# Sheet1.net
KiCad netlist of a schematic drawn in Altium Designer
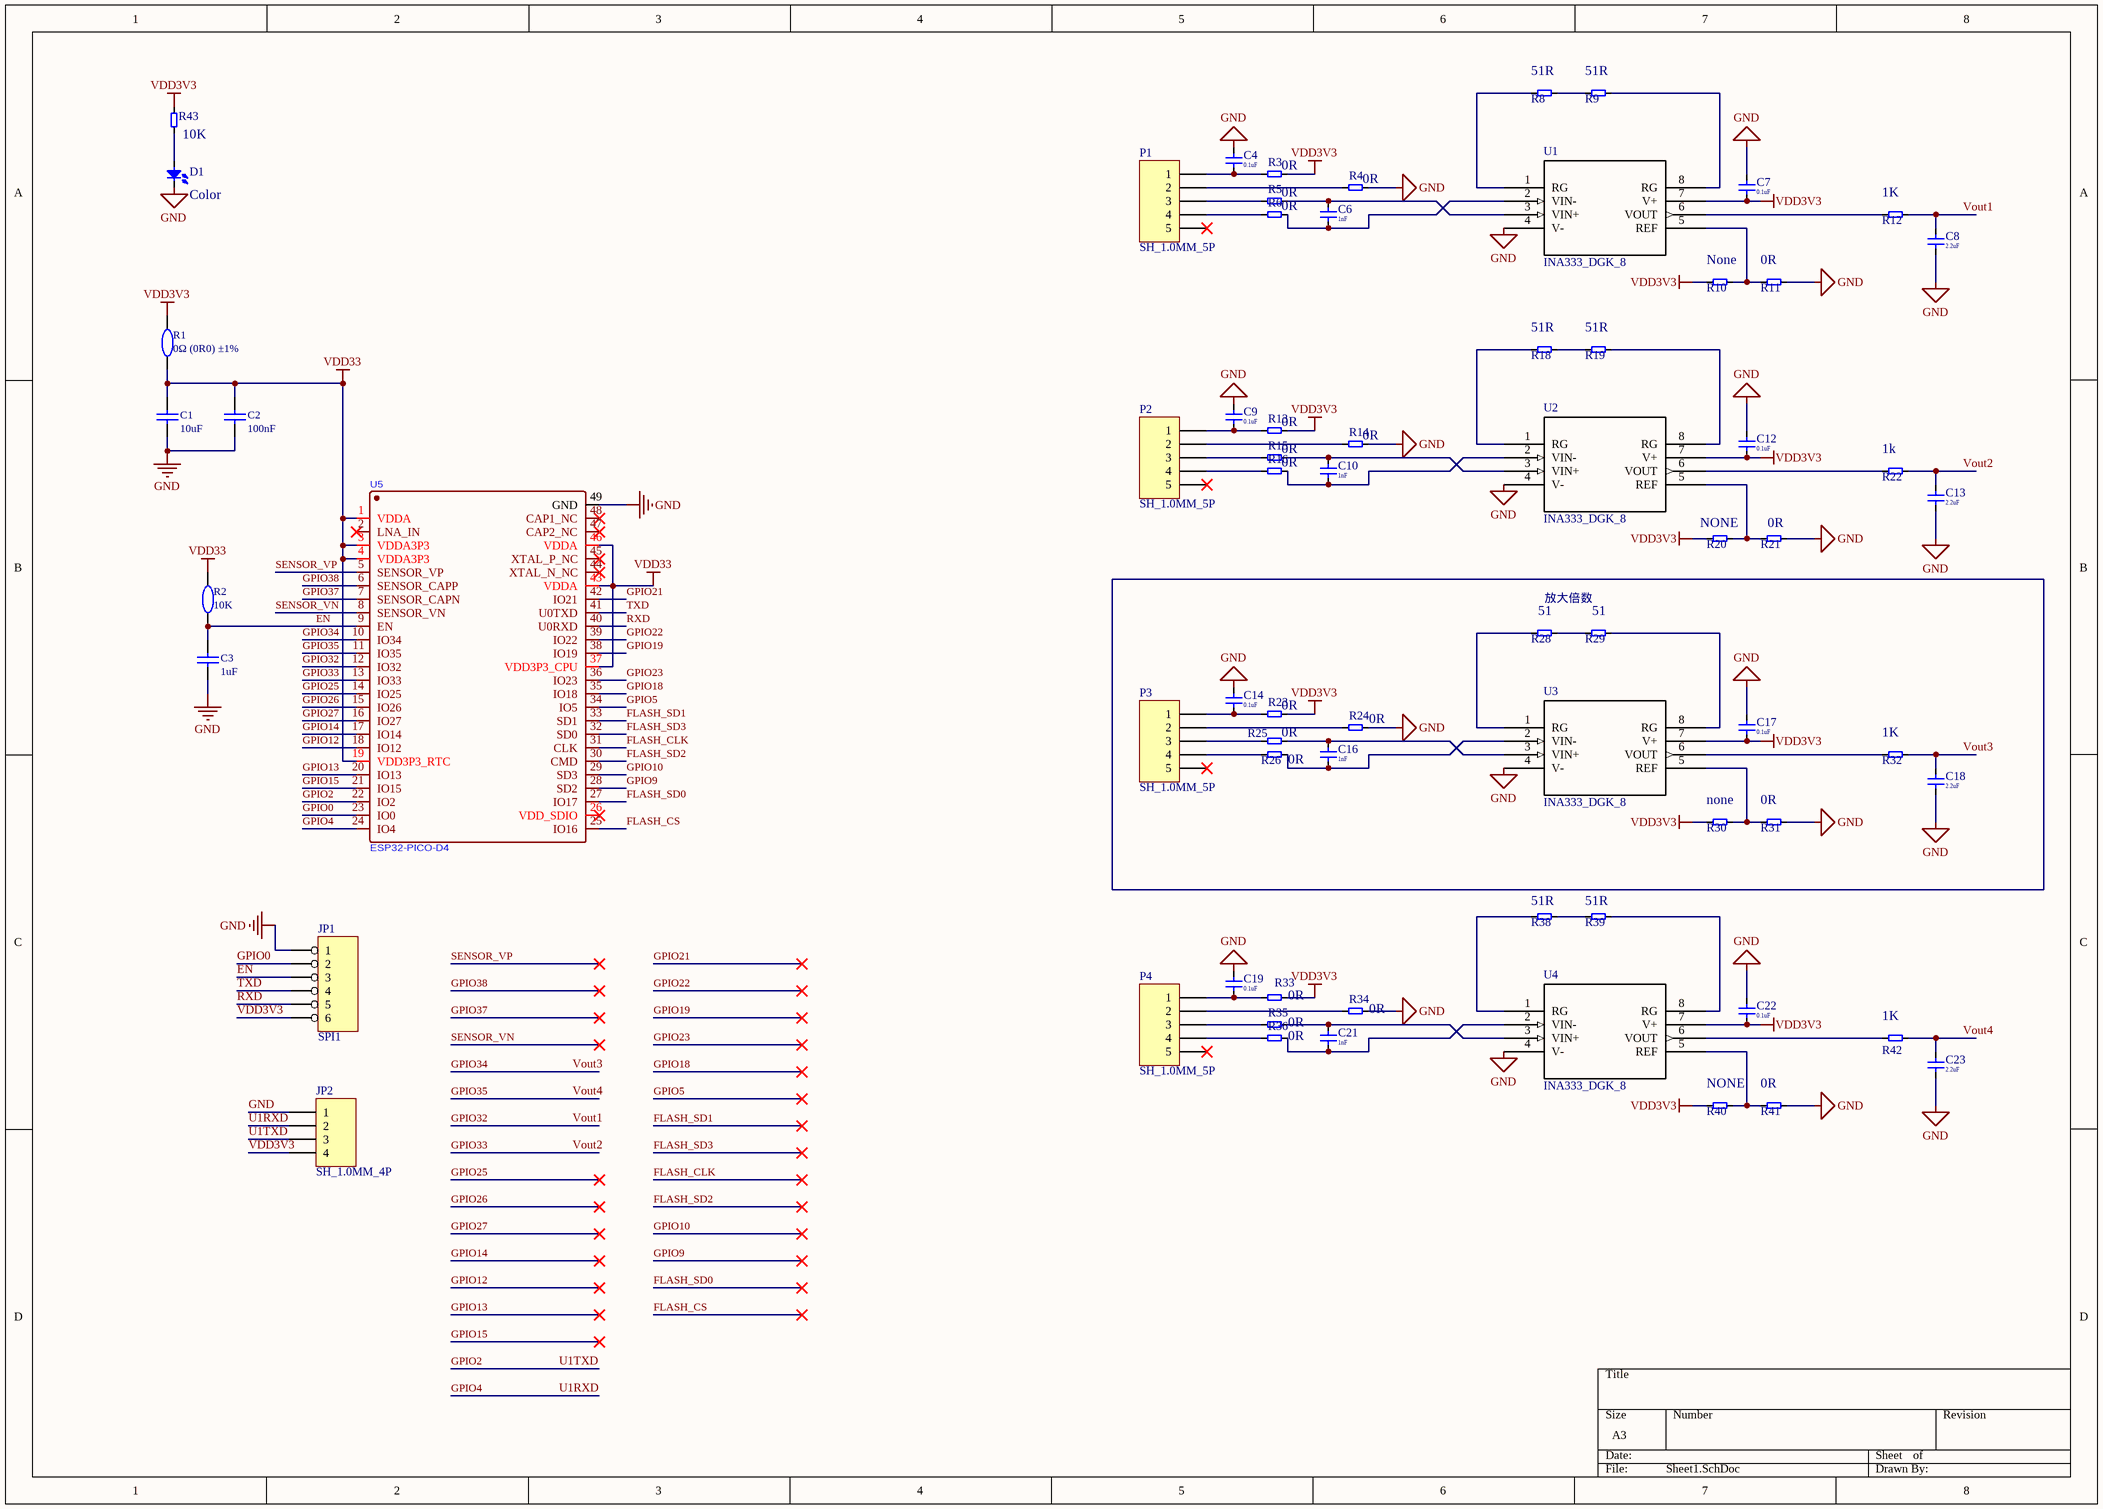
[diagram p0: Sheet1.SchDoc]

(export (version "E")
  (design (tool "Eeschema 10.0.6"))
  (components
    (comp (ref "C1")
      (value "10uF")
      (footprint "0603C")
      (libsource (lib "altium-import") (part "root_1_10uF_"))
    )
    (comp (ref "C2")
      (value "100nF")
      (footprint "0603C")
      (libsource (lib "altium-import") (part "root_1_100nF_"))
    )
    (comp (ref "C3") (value "1uF") (footprint "0603C") (libsource (lib "altium-import") (part "root_1_1uF_")))
    (comp (ref "C4")
      (value "0.1uF")
      (footprint "0603C")
      (fields (field (name "Comment") "Cb"))
      (libsource (lib "RCL") (part "Cap0603"))
    )
    (comp (ref "C6")
      (value "1nF")
      (footprint "0603C")
      (fields (field (name "Comment") "Cb"))
      (libsource (lib "RCL") (part "Cap0603"))
    )
    (comp (ref "C7")
      (value "0.1uF")
      (footprint "0603C")
      (fields (field (name "Comment") "Cb"))
      (libsource (lib "RCL") (part "Cap0603"))
    )
    (comp (ref "C8")
      (value "2.2uF")
      (footprint "0603C")
      (fields (field (name "Comment") "Cb"))
      (libsource (lib "RCL") (part "Cap0603"))
    )
    (comp (ref "C9")
      (value "0.1uF")
      (footprint "0603C")
      (fields (field (name "Comment") "Cb"))
      (libsource (lib "RCL") (part "Cap0603"))
    )
    (comp (ref "C10")
      (value "1nF")
      (footprint "0603C")
      (fields (field (name "Comment") "Cb"))
      (libsource (lib "RCL") (part "Cap0603"))
    )
    (comp (ref "C12")
      (value "0.1uF")
      (footprint "0603C")
      (fields (field (name "Comment") "Cb"))
      (libsource (lib "RCL") (part "Cap0603"))
    )
    (comp (ref "C13")
      (value "2.2uF")
      (footprint "0603C")
      (fields (field (name "Comment") "Cb"))
      (libsource (lib "RCL") (part "Cap0603"))
    )
    (comp (ref "C14")
      (value "0.1uF")
      (footprint "0603C")
      (fields (field (name "Comment") "Cb"))
      (libsource (lib "RCL") (part "Cap0603"))
    )
    (comp (ref "C16")
      (value "1nF")
      (footprint "0603C")
      (fields (field (name "Comment") "Cb"))
      (libsource (lib "RCL") (part "Cap0603"))
    )
    (comp (ref "C17")
      (value "0.1uF")
      (footprint "0603C")
      (fields (field (name "Comment") "Cb"))
      (libsource (lib "RCL") (part "Cap0603"))
    )
    (comp (ref "C18")
      (value "2.2uF")
      (footprint "0603C")
      (fields (field (name "Comment") "Cb"))
      (libsource (lib "RCL") (part "Cap0603"))
    )
    (comp (ref "C19")
      (value "0.1uF")
      (footprint "0603C")
      (fields (field (name "Comment") "Cb"))
      (libsource (lib "RCL") (part "Cap0603"))
    )
    (comp (ref "C21")
      (value "1nF")
      (footprint "0603C")
      (fields (field (name "Comment") "Cb"))
      (libsource (lib "RCL") (part "Cap0603"))
    )
    (comp (ref "C22")
      (value "0.1uF")
      (footprint "0603C")
      (fields (field (name "Comment") "0.1μF"))
      (libsource (lib "RCL") (part "Cap0603"))
    )
    (comp (ref "C23")
      (value "2.2uF")
      (footprint "0603C")
      (fields (field (name "Comment") "2.2μF"))
      (libsource (lib "RCL") (part "Cap0603"))
    )
    (comp (ref "D1")
      (value "Color")
      (footprint "0603Led")
      (fields (field (name "Comment") "LED0603"))
      (libsource (lib "RCL") (part "LED0603"))
    )
    (comp (ref "JP1") (value "SPI1") (footprint "SHDR6") (libsource (lib "刘涛20200314") (part "HEADER 6")))
    (comp (ref "JP2")
      (value "SH_1.0MM_4P")
      (footprint "SH_1.0MM_4P")
      (fields (field (name "PUBLISHER") "Altium Limited"))
      (libsource (lib "foot") (part "SH_1.0MM_4P"))
    )
    (comp (ref "P1")
      (value "SH_1.0MM_5P")
      (footprint "SH_1.0MM_5P")
      (fields (field (name "PUBLISHER") "Altium Limited"))
      (libsource (lib "AOO") (part "SH_1.0MM_5P"))
    )
    (comp (ref "P2")
      (value "SH_1.0MM_5P")
      (footprint "SH_1.0MM_5P")
      (fields (field (name "PUBLISHER") "Altium Limited"))
      (libsource (lib "AOO") (part "SH_1.0MM_5P"))
    )
    (comp (ref "P3")
      (value "SH_1.0MM_5P")
      (footprint "SH_1.0MM_5P")
      (fields (field (name "PUBLISHER") "Altium Limited"))
      (libsource (lib "AOO") (part "SH_1.0MM_5P"))
    )
    (comp (ref "P4")
      (value "SH_1.0MM_5P")
      (footprint "SH_1.0MM_5P")
      (fields (field (name "PUBLISHER") "Altium Limited"))
      (libsource (lib "AOO") (part "SH_1.0MM_5P"))
    )
    (comp (ref "R1")
      (value "0Ω (0R0) ±1%")
      (footprint "0603R")
      (libsource (lib "altium-import") (part "root_1_0Ω (0R0) ±1%_"))
    )
    (comp (ref "R2") (value "10K") (footprint "0603R") (libsource (lib "altium-import") (part "root_1_10K_")))
    (comp (ref "R3")
      (value "0R")
      (footprint "0603R")
      (fields (field (name "Comment") "Rb"))
      (libsource (lib "") (part "Res0603_1"))
    )
    (comp (ref "R4")
      (value "0R")
      (footprint "0603R")
      (fields (field (name "Comment") "Rb"))
      (libsource (lib "") (part "Res0603_1"))
    )
    (comp (ref "R5")
      (value "0R")
      (footprint "0603R")
      (fields (field (name "Comment") "Rb"))
      (libsource (lib "") (part "Res0603_1"))
    )
    (comp (ref "R6")
      (value "0R")
      (footprint "0603R")
      (fields (field (name "Comment") "Rb"))
      (libsource (lib "") (part "Res0603_1"))
    )
    (comp (ref "R8")
      (value "51R")
      (footprint "0603R")
      (fields (field (name "Comment") "Rb"))
      (libsource (lib "RCL") (part "Res0603"))
    )
    (comp (ref "R9")
      (value "51R")
      (footprint "0603R")
      (fields (field (name "Comment") "Rb"))
      (libsource (lib "RCL") (part "Res0603"))
    )
    (comp (ref "R10")
      (value "None")
      (footprint "0603R")
      (fields (field (name "Comment") "Rb"))
      (libsource (lib "RCL") (part "Res0603"))
    )
    (comp (ref "R11")
      (value "0R")
      (footprint "0603R")
      (fields (field (name "Comment") "Rb"))
      (libsource (lib "RCL") (part "Res0603"))
    )
    (comp (ref "R12")
      (value "1K")
      (footprint "0603R")
      (fields (field (name "Comment") "Rb"))
      (libsource (lib "RCL") (part "Res0603"))
    )
    (comp (ref "R13")
      (value "0R")
      (footprint "0603R")
      (fields (field (name "Comment") "Rb"))
      (libsource (lib "") (part "Res0603_1"))
    )
    (comp (ref "R14")
      (value "0R")
      (footprint "0603R")
      (fields (field (name "Comment") "Rb"))
      (libsource (lib "") (part "Res0603_1"))
    )
    (comp (ref "R15")
      (value "0R")
      (footprint "0603R")
      (fields (field (name "Comment") "Rb"))
      (libsource (lib "") (part "Res0603_1"))
    )
    (comp (ref "R16")
      (value "0R")
      (footprint "0603R")
      (fields (field (name "Comment") "Rb"))
      (libsource (lib "") (part "Res0603_1"))
    )
    (comp (ref "R18")
      (value "51R")
      (footprint "0603R")
      (fields (field (name "Comment") "Rb"))
      (libsource (lib "RCL") (part "Res0603"))
    )
    (comp (ref "R19")
      (value "51R")
      (footprint "0603R")
      (fields (field (name "Comment") "Rb"))
      (libsource (lib "RCL") (part "Res0603"))
    )
    (comp (ref "R20")
      (value "NONE")
      (footprint "0603R")
      (fields (field (name "Comment") "Rb"))
      (libsource (lib "RCL") (part "Res0603"))
    )
    (comp (ref "R21")
      (value "0R")
      (footprint "0603R")
      (fields (field (name "Comment") "Rb"))
      (libsource (lib "RCL") (part "Res0603"))
    )
    (comp (ref "R22")
      (value "1k")
      (footprint "0603R")
      (fields (field (name "Comment") "Rb"))
      (libsource (lib "RCL") (part "Res0603"))
    )
    (comp (ref "R23")
      (value "0R")
      (footprint "0603R")
      (fields (field (name "Comment") "Rb"))
      (libsource (lib "") (part "Res0603_1"))
    )
    (comp (ref "R24")
      (value "0R")
      (footprint "0603R")
      (fields (field (name "Comment") "Rb"))
      (libsource (lib "") (part "Res0603_1"))
    )
    (comp (ref "R25")
      (value "0R")
      (footprint "0603R")
      (fields (field (name "Comment") "Rb"))
      (libsource (lib "") (part "Res0603_1"))
    )
    (comp (ref "R26")
      (value "0R")
      (footprint "0603R")
      (fields (field (name "Comment") "Rb"))
      (libsource (lib "") (part "Res0603_1"))
    )
    (comp (ref "R28")
      (value "51")
      (footprint "0603R")
      (fields (field (name "Comment") "Rb"))
      (libsource (lib "RCL") (part "Res0603"))
    )
    (comp (ref "R29")
      (value "51")
      (footprint "0603R")
      (fields (field (name "Comment") "Rb"))
      (libsource (lib "RCL") (part "Res0603"))
    )
    (comp (ref "R30")
      (value "none")
      (footprint "0603R")
      (fields (field (name "Comment") "Rb"))
      (libsource (lib "RCL") (part "Res0603"))
    )
    (comp (ref "R31")
      (value "0R")
      (footprint "0603R")
      (fields (field (name "Comment") "Rb"))
      (libsource (lib "RCL") (part "Res0603"))
    )
    (comp (ref "R32")
      (value "1K")
      (footprint "0603R")
      (fields (field (name "Comment") "Rb"))
      (libsource (lib "RCL") (part "Res0603"))
    )
    (comp (ref "R33")
      (value "0R")
      (footprint "0603R")
      (fields (field (name "Comment") "Rb"))
      (libsource (lib "") (part "Res0603_1"))
    )
    (comp (ref "R34")
      (value "0R")
      (footprint "0603R")
      (fields (field (name "Comment") "Rb"))
      (libsource (lib "") (part "Res0603_1"))
    )
    (comp (ref "R35")
      (value "0R")
      (footprint "0603R")
      (fields (field (name "Comment") "Rb"))
      (libsource (lib "") (part "Res0603_1"))
    )
    (comp (ref "R36")
      (value "0R")
      (footprint "0603R")
      (fields (field (name "Comment") "Rb"))
      (libsource (lib "") (part "Res0603_1"))
    )
    (comp (ref "R38")
      (value "51R")
      (footprint "0603R")
      (fields (field (name "Comment") "Rb"))
      (libsource (lib "RCL") (part "Res0603"))
    )
    (comp (ref "R39")
      (value "51R")
      (footprint "0603R")
      (fields (field (name "Comment") "51"))
      (libsource (lib "RCL") (part "Res0603"))
    )
    (comp (ref "R40")
      (value "NONE")
      (footprint "0603R")
      (fields (field (name "Comment") "Rb"))
      (libsource (lib "RCL") (part "Res0603"))
    )
    (comp (ref "R41")
      (value "0R")
      (footprint "0603R")
      (fields (field (name "Comment") "0Ω"))
      (libsource (lib "RCL") (part "Res0603"))
    )
    (comp (ref "R42") (value "1K") (footprint "0603R") (libsource (lib "RCL") (part "Res0603")))
    (comp (ref "R43") (value "10K") (footprint "0603R") (libsource (lib "") (part "Res0603_2")))
    (comp (ref "U1")
      (value "INA333_DGK_8")
      (footprint "VSSOP-8")
      (description "Imported")
      (fields (field (name "MANUFACTURER") "Texas Instruments") (field (name "GENERIC_PART_NUMBER") "INA333"))
      (libsource (lib "ICS") (part "INA333_DGK_8"))
    )
    (comp (ref "U2")
      (value "INA333_DGK_8")
      (footprint "VSSOP-8")
      (description "Imported")
      (fields (field (name "MANUFACTURER") "Texas Instruments") (field (name "GENERIC_PART_NUMBER") "INA333"))
      (libsource (lib "ICS") (part "INA333_DGK_8"))
    )
    (comp (ref "U3")
      (value "INA333_DGK_8")
      (footprint "VSSOP-8")
      (description "Imported")
      (fields (field (name "MANUFACTURER") "Texas Instruments") (field (name "GENERIC_PART_NUMBER") "INA333"))
      (libsource (lib "ICS") (part "INA333_DGK_8"))
    )
    (comp (ref "U4")
      (value "INA333_DGK_8")
      (footprint "VSSOP-8")
      (description "Imported")
      (fields (field (name "MANUFACTURER") "Texas Instruments") (field (name "GENERIC_PART_NUMBER") "INA333"))
      (libsource (lib "ICS") (part "INA333_DGK_8"))
    )
    (comp (ref "U5")
      (value "ESP32-PICO-D4")
      (footprint "PICO")
      (libsource (lib "altium-import") (part "root_0_ESP32-PICO-D4_"))
    )
  )
  (nets
    (net (code "1") (name "/EN") (class "Default")
      (node (ref "C3") (pin "2") (pinfunction "2_2") (pintype "passive"))
      (node (ref "JP1") (pin "3") (pinfunction "3_3") (pintype "passive"))
      (node (ref "R2") (pin "1") (pinfunction "1_1") (pintype "passive"))
      (node (ref "U5") (pin "9") (pinfunction "EN_9") (pintype "passive"))
    )
    (net (code "2") (name "/FLASH_CLK") (class "Default")
      (node (ref "U5") (pin "31") (pinfunction "CLK_31") (pintype "passive+no_connect"))
    )
    (net (code "3") (name "/FLASH_CS") (class "Default")
      (node (ref "U5") (pin "25") (pinfunction "IO16_25") (pintype "passive+no_connect"))
    )
    (net (code "4") (name "/FLASH_SD0") (class "Default")
      (node (ref "U5") (pin "27") (pinfunction "IO17_27") (pintype "passive+no_connect"))
    )
    (net (code "5") (name "/FLASH_SD1") (class "Default")
      (node (ref "U5") (pin "33") (pinfunction "SD1_33") (pintype "passive+no_connect"))
    )
    (net (code "6") (name "/FLASH_SD2") (class "Default")
      (node (ref "U5") (pin "30") (pinfunction "CMD_30") (pintype "passive+no_connect"))
    )
    (net (code "7") (name "/FLASH_SD3") (class "Default")
      (node (ref "U5") (pin "32") (pinfunction "SD0_32") (pintype "passive+no_connect"))
    )
    (net (code "8") (name "/GPIO0") (class "Default")
      (node (ref "JP1") (pin "2") (pinfunction "2_2") (pintype "passive"))
      (node (ref "U5") (pin "23") (pinfunction "IO0_23") (pintype "passive"))
    )
    (net (code "9") (name "/GPIO2") (class "Default")
      (node (ref "JP2") (pin "3") (pinfunction "3_3") (pintype "passive"))
      (node (ref "U5") (pin "22") (pinfunction "IO2_22") (pintype "passive"))
    )
    (net (code "10") (name "/GPIO4") (class "Default")
      (node (ref "JP2") (pin "2") (pinfunction "2_2") (pintype "passive"))
      (node (ref "U5") (pin "24") (pinfunction "IO4_24") (pintype "passive"))
    )
    (net (code "11") (name "/GPIO5") (class "Default")
      (node (ref "U5") (pin "34") (pinfunction "IO5_34") (pintype "passive+no_connect"))
    )
    (net (code "12") (name "/GPIO9") (class "Default")
      (node (ref "U5") (pin "28") (pinfunction "SD2_28") (pintype "passive+no_connect"))
    )
    (net (code "13") (name "/GPIO10") (class "Default")
      (node (ref "U5") (pin "29") (pinfunction "SD3_29") (pintype "passive+no_connect"))
    )
    (net (code "14") (name "/GPIO12") (class "Default")
      (node (ref "U5") (pin "18") (pinfunction "IO12_18") (pintype "passive+no_connect"))
    )
    (net (code "15") (name "/GPIO13") (class "Default")
      (node (ref "U5") (pin "20") (pinfunction "IO13_20") (pintype "passive+no_connect"))
    )
    (net (code "16") (name "/GPIO14") (class "Default")
      (node (ref "U5") (pin "17") (pinfunction "IO14_17") (pintype "passive+no_connect"))
    )
    (net (code "17") (name "/GPIO15") (class "Default")
      (node (ref "U5") (pin "21") (pinfunction "IO15_21") (pintype "passive+no_connect"))
    )
    (net (code "18") (name "/GPIO18") (class "Default")
      (node (ref "U5") (pin "35") (pinfunction "IO18_35") (pintype "passive"))
    )
    (net (code "19") (name "/GPIO19") (class "Default")
      (node (ref "U5") (pin "38") (pinfunction "IO19_38") (pintype "passive"))
    )
    (net (code "20") (name "/GPIO21") (class "Default")
      (node (ref "U5") (pin "42") (pinfunction "IO21_42") (pintype "passive"))
    )
    (net (code "21") (name "/GPIO22") (class "Default")
      (node (ref "U5") (pin "39") (pinfunction "IO22_39") (pintype "passive"))
    )
    (net (code "22") (name "/GPIO23") (class "Default")
      (node (ref "U5") (pin "36") (pinfunction "IO23_36") (pintype "passive"))
    )
    (net (code "23") (name "/GPIO25") (class "Default")
      (node (ref "U5") (pin "14") (pinfunction "IO25_14") (pintype "passive+no_connect"))
    )
    (net (code "24") (name "/GPIO26") (class "Default")
      (node (ref "U5") (pin "15") (pinfunction "IO26_15") (pintype "passive+no_connect"))
    )
    (net (code "25") (name "/GPIO27") (class "Default")
      (node (ref "U5") (pin "16") (pinfunction "IO27_16") (pintype "passive+no_connect"))
    )
    (net (code "26") (name "/GPIO32") (class "Default")
      (node (ref "C8") (pin "2") (pinfunction "2_2") (pintype "passive"))
      (node (ref "R12") (pin "2") (pinfunction "2_2") (pintype "passive"))
      (node (ref "U5") (pin "12") (pinfunction "IO32_12") (pintype "passive"))
    )
    (net (code "27") (name "/GPIO33") (class "Default")
      (node (ref "C13") (pin "2") (pinfunction "2_2") (pintype "passive"))
      (node (ref "R22") (pin "2") (pinfunction "2_2") (pintype "passive"))
      (node (ref "U5") (pin "13") (pinfunction "IO33_13") (pintype "passive"))
    )
    (net (code "28") (name "/GPIO34") (class "Default")
      (node (ref "C18") (pin "2") (pinfunction "2_2") (pintype "passive"))
      (node (ref "R32") (pin "2") (pinfunction "2_2") (pintype "passive"))
      (node (ref "U5") (pin "10") (pinfunction "IO34_10") (pintype "passive"))
    )
    (net (code "29") (name "/GPIO35") (class "Default")
      (node (ref "C23") (pin "2") (pinfunction "2_2") (pintype "passive"))
      (node (ref "R42") (pin "2") (pinfunction "2_2") (pintype "passive"))
      (node (ref "U5") (pin "11") (pinfunction "IO35_11") (pintype "passive"))
    )
    (net (code "30") (name "/GPIO37") (class "Default")
      (node (ref "U5") (pin "7") (pinfunction "SENSOR_CAPN_7") (pintype "passive"))
    )
    (net (code "31") (name "/GPIO38") (class "Default")
      (node (ref "U5") (pin "6") (pinfunction "SENSOR_CAPP_6") (pintype "passive"))
    )
    (net (code "32") (name "/RXD") (class "Default")
      (node (ref "JP1") (pin "5") (pinfunction "5_5") (pintype "passive"))
      (node (ref "U5") (pin "40") (pinfunction "U0RXD_40") (pintype "passive"))
    )
    (net (code "33") (name "/SENSOR_VN") (class "Default")
      (node (ref "U5") (pin "8") (pinfunction "SENSOR_VN_8") (pintype "passive"))
    )
    (net (code "34") (name "/SENSOR_VP") (class "Default")
      (node (ref "U5") (pin "5") (pinfunction "SENSOR_VP_5") (pintype "passive"))
    )
    (net (code "35") (name "/TXD") (class "Default")
      (node (ref "JP1") (pin "4") (pinfunction "4_4") (pintype "passive"))
      (node (ref "U5") (pin "41") (pinfunction "U0TXD_41") (pintype "passive"))
    )
    (net (code "36") (name "GND") (class "Default")
      (node (ref "C1") (pin "1") (pinfunction "1_1") (pintype "passive"))
      (node (ref "C12") (pin "2") (pinfunction "2_2") (pintype "passive"))
      (node (ref "C13") (pin "1") (pinfunction "1_1") (pintype "passive"))
      (node (ref "C14") (pin "1") (pinfunction "1_1") (pintype "passive"))
      (node (ref "C17") (pin "2") (pinfunction "2_2") (pintype "passive"))
      (node (ref "C18") (pin "1") (pinfunction "1_1") (pintype "passive"))
      (node (ref "C19") (pin "1") (pinfunction "1_1") (pintype "passive"))
      (node (ref "C2") (pin "1") (pinfunction "1_1") (pintype "passive"))
      (node (ref "C22") (pin "2") (pinfunction "2_2") (pintype "passive"))
      (node (ref "C23") (pin "1") (pinfunction "1_1") (pintype "passive"))
      (node (ref "C3") (pin "1") (pinfunction "1_1") (pintype "passive"))
      (node (ref "C4") (pin "1") (pinfunction "1_1") (pintype "passive"))
      (node (ref "C7") (pin "2") (pinfunction "2_2") (pintype "passive"))
      (node (ref "C8") (pin "1") (pinfunction "1_1") (pintype "passive"))
      (node (ref "C9") (pin "1") (pinfunction "1_1") (pintype "passive"))
      (node (ref "D1") (pin "1") (pinfunction "1_1") (pintype "passive"))
      (node (ref "JP1") (pin "1") (pinfunction "1_1") (pintype "passive"))
      (node (ref "JP2") (pin "1") (pinfunction "1_1") (pintype "passive"))
      (node (ref "R11") (pin "2") (pinfunction "2_2") (pintype "passive"))
      (node (ref "R14") (pin "1") (pinfunction "1_1") (pintype "passive"))
      (node (ref "R21") (pin "2") (pinfunction "2_2") (pintype "passive"))
      (node (ref "R24") (pin "1") (pinfunction "1_1") (pintype "passive"))
      (node (ref "R31") (pin "2") (pinfunction "2_2") (pintype "passive"))
      (node (ref "R34") (pin "1") (pinfunction "1_1") (pintype "passive"))
      (node (ref "R4") (pin "1") (pinfunction "1_1") (pintype "passive"))
      (node (ref "R41") (pin "2") (pinfunction "2_2") (pintype "passive"))
      (node (ref "U1") (pin "4") (pinfunction "V-_4") (pintype "power_in"))
      (node (ref "U2") (pin "4") (pinfunction "V-_4") (pintype "power_in"))
      (node (ref "U3") (pin "4") (pinfunction "V-_4") (pintype "power_in"))
      (node (ref "U4") (pin "4") (pinfunction "V-_4") (pintype "power_in"))
      (node (ref "U5") (pin "49") (pinfunction "GND_49") (pintype "passive"))
    )
    (net (code "37") (name "Net-(C4-Pad2)") (class "Default")
      (node (ref "C4") (pin "2") (pinfunction "2_2") (pintype "passive"))
      (node (ref "P1") (pin "1") (pinfunction "1_1") (pintype "passive"))
      (node (ref "R3") (pin "2") (pinfunction "2_2") (pintype "passive"))
    )
    (net (code "38") (name "Net-(C9-Pad2)") (class "Default")
      (node (ref "C9") (pin "2") (pinfunction "2_2") (pintype "passive"))
      (node (ref "P2") (pin "1") (pinfunction "1_1") (pintype "passive"))
      (node (ref "R13") (pin "2") (pinfunction "2_2") (pintype "passive"))
    )
    (net (code "39") (name "Net-(C14-Pad2)") (class "Default")
      (node (ref "C14") (pin "2") (pinfunction "2_2") (pintype "passive"))
      (node (ref "P3") (pin "1") (pinfunction "1_1") (pintype "passive"))
      (node (ref "R23") (pin "2") (pinfunction "2_2") (pintype "passive"))
    )
    (net (code "40") (name "Net-(C19-Pad2)") (class "Default")
      (node (ref "C19") (pin "2") (pinfunction "2_2") (pintype "passive"))
      (node (ref "P4") (pin "1") (pinfunction "1_1") (pintype "passive"))
      (node (ref "R33") (pin "2") (pinfunction "2_2") (pintype "passive"))
    )
    (net (code "41") (name "Net-(D1-Pad2)") (class "Default")
      (node (ref "D1") (pin "2") (pinfunction "2_2") (pintype "passive"))
      (node (ref "R43") (pin "2") (pinfunction "2_2") (pintype "passive"))
    )
    (net (code "42") (name "Net-(P1-Pad2)") (class "Default")
      (node (ref "P1") (pin "2") (pinfunction "2_2") (pintype "passive"))
      (node (ref "R4") (pin "2") (pinfunction "2_2") (pintype "passive"))
    )
    (net (code "43") (name "Net-(P1-Pad3)") (class "Default")
      (node (ref "P1") (pin "3") (pinfunction "3_3") (pintype "passive"))
      (node (ref "R5") (pin "2") (pinfunction "2_2") (pintype "passive"))
    )
    (net (code "44") (name "Net-(P1-Pad4)") (class "Default")
      (node (ref "P1") (pin "4") (pinfunction "4_4") (pintype "passive"))
      (node (ref "R6") (pin "2") (pinfunction "2_2") (pintype "passive"))
    )
    (net (code "45") (name "Net-(P2-Pad2)") (class "Default")
      (node (ref "P2") (pin "2") (pinfunction "2_2") (pintype "passive"))
      (node (ref "R14") (pin "2") (pinfunction "2_2") (pintype "passive"))
    )
    (net (code "46") (name "Net-(P2-Pad3)") (class "Default")
      (node (ref "P2") (pin "3") (pinfunction "3_3") (pintype "passive"))
      (node (ref "R15") (pin "2") (pinfunction "2_2") (pintype "passive"))
    )
    (net (code "47") (name "Net-(P2-Pad4)") (class "Default")
      (node (ref "P2") (pin "4") (pinfunction "4_4") (pintype "passive"))
      (node (ref "R16") (pin "2") (pinfunction "2_2") (pintype "passive"))
    )
    (net (code "48") (name "Net-(P3-Pad2)") (class "Default")
      (node (ref "P3") (pin "2") (pinfunction "2_2") (pintype "passive"))
      (node (ref "R24") (pin "2") (pinfunction "2_2") (pintype "passive"))
    )
    (net (code "49") (name "Net-(P3-Pad3)") (class "Default")
      (node (ref "P3") (pin "3") (pinfunction "3_3") (pintype "passive"))
      (node (ref "R25") (pin "2") (pinfunction "2_2") (pintype "passive"))
    )
    (net (code "50") (name "Net-(P3-Pad4)") (class "Default")
      (node (ref "P3") (pin "4") (pinfunction "4_4") (pintype "passive"))
      (node (ref "R26") (pin "2") (pinfunction "2_2") (pintype "passive"))
    )
    (net (code "51") (name "Net-(P4-Pad2)") (class "Default")
      (node (ref "P4") (pin "2") (pinfunction "2_2") (pintype "passive"))
      (node (ref "R34") (pin "2") (pinfunction "2_2") (pintype "passive"))
    )
    (net (code "52") (name "Net-(P4-Pad3)") (class "Default")
      (node (ref "P4") (pin "3") (pinfunction "3_3") (pintype "passive"))
      (node (ref "R35") (pin "2") (pinfunction "2_2") (pintype "passive"))
    )
    (net (code "53") (name "Net-(P4-Pad4)") (class "Default")
      (node (ref "P4") (pin "4") (pinfunction "4_4") (pintype "passive"))
      (node (ref "R36") (pin "2") (pinfunction "2_2") (pintype "passive"))
    )
    (net (code "54") (name "Net-(R8-Pad1)") (class "Default")
      (node (ref "R8") (pin "1") (pinfunction "1_1") (pintype "passive"))
      (node (ref "U1") (pin "1") (pinfunction "RG_1") (pintype "passive"))
    )
    (net (code "55") (name "Net-(R8-Pad2)") (class "Default")
      (node (ref "R8") (pin "2") (pinfunction "2_2") (pintype "passive"))
      (node (ref "R9") (pin "1") (pinfunction "1_1") (pintype "passive"))
    )
    (net (code "56") (name "Net-(R9-Pad2)") (class "Default")
      (node (ref "R9") (pin "2") (pinfunction "2_2") (pintype "passive"))
      (node (ref "U1") (pin "8") (pinfunction "RG_8") (pintype "passive"))
    )
    (net (code "57") (name "Net-(R18-Pad1)") (class "Default")
      (node (ref "R18") (pin "1") (pinfunction "1_1") (pintype "passive"))
      (node (ref "U2") (pin "1") (pinfunction "RG_1") (pintype "passive"))
    )
    (net (code "58") (name "Net-(R18-Pad2)") (class "Default")
      (node (ref "R18") (pin "2") (pinfunction "2_2") (pintype "passive"))
      (node (ref "R19") (pin "1") (pinfunction "1_1") (pintype "passive"))
    )
    (net (code "59") (name "Net-(R19-Pad2)") (class "Default")
      (node (ref "R19") (pin "2") (pinfunction "2_2") (pintype "passive"))
      (node (ref "U2") (pin "8") (pinfunction "RG_8") (pintype "passive"))
    )
    (net (code "60") (name "Net-(R28-Pad1)") (class "Default")
      (node (ref "R28") (pin "1") (pinfunction "1_1") (pintype "passive"))
      (node (ref "U3") (pin "1") (pinfunction "RG_1") (pintype "passive"))
    )
    (net (code "61") (name "Net-(R28-Pad2)") (class "Default")
      (node (ref "R28") (pin "2") (pinfunction "2_2") (pintype "passive"))
      (node (ref "R29") (pin "1") (pinfunction "1_1") (pintype "passive"))
    )
    (net (code "62") (name "Net-(R29-Pad2)") (class "Default")
      (node (ref "R29") (pin "2") (pinfunction "2_2") (pintype "passive"))
      (node (ref "U3") (pin "8") (pinfunction "RG_8") (pintype "passive"))
    )
    (net (code "63") (name "Net-(R38-Pad1)") (class "Default")
      (node (ref "R38") (pin "1") (pinfunction "1_1") (pintype "passive"))
      (node (ref "U4") (pin "1") (pinfunction "RG_1") (pintype "passive"))
    )
    (net (code "64") (name "Net-(R38-Pad2)") (class "Default")
      (node (ref "R38") (pin "2") (pinfunction "2_2") (pintype "passive"))
      (node (ref "R39") (pin "1") (pinfunction "1_1") (pintype "passive"))
    )
    (net (code "65") (name "Net-(R39-Pad2)") (class "Default")
      (node (ref "R39") (pin "2") (pinfunction "2_2") (pintype "passive"))
      (node (ref "U4") (pin "8") (pinfunction "RG_8") (pintype "passive"))
    )
    (net (code "66") (name "Net-(U1-REF)") (class "Default")
      (node (ref "R10") (pin "2") (pinfunction "2_2") (pintype "passive"))
      (node (ref "R11") (pin "1") (pinfunction "1_1") (pintype "passive"))
      (node (ref "U1") (pin "5") (pinfunction "REF_5") (pintype "passive"))
    )
    (net (code "67") (name "Net-(U1-VIN+)") (class "Default")
      (node (ref "C6") (pin "2") (pinfunction "2_2") (pintype "passive"))
      (node (ref "R5") (pin "1") (pinfunction "1_1") (pintype "passive"))
      (node (ref "U1") (pin "3") (pinfunction "VIN+_3") (pintype "input"))
    )
    (net (code "68") (name "Net-(U1-VIN-)") (class "Default")
      (node (ref "C6") (pin "1") (pinfunction "1_1") (pintype "passive"))
      (node (ref "R6") (pin "1") (pinfunction "1_1") (pintype "passive"))
      (node (ref "U1") (pin "2") (pinfunction "VIN-_2") (pintype "input"))
    )
    (net (code "69") (name "Net-(U1-VOUT)") (class "Default")
      (node (ref "R12") (pin "1") (pinfunction "1_1") (pintype "passive"))
      (node (ref "U1") (pin "6") (pinfunction "VOUT_6") (pintype "output"))
    )
    (net (code "70") (name "Net-(U2-REF)") (class "Default")
      (node (ref "R20") (pin "2") (pinfunction "2_2") (pintype "passive"))
      (node (ref "R21") (pin "1") (pinfunction "1_1") (pintype "passive"))
      (node (ref "U2") (pin "5") (pinfunction "REF_5") (pintype "passive"))
    )
    (net (code "71") (name "Net-(U2-VIN+)") (class "Default")
      (node (ref "C10") (pin "2") (pinfunction "2_2") (pintype "passive"))
      (node (ref "R15") (pin "1") (pinfunction "1_1") (pintype "passive"))
      (node (ref "U2") (pin "3") (pinfunction "VIN+_3") (pintype "input"))
    )
    (net (code "72") (name "Net-(U2-VIN-)") (class "Default")
      (node (ref "C10") (pin "1") (pinfunction "1_1") (pintype "passive"))
      (node (ref "R16") (pin "1") (pinfunction "1_1") (pintype "passive"))
      (node (ref "U2") (pin "2") (pinfunction "VIN-_2") (pintype "input"))
    )
    (net (code "73") (name "Net-(U2-VOUT)") (class "Default")
      (node (ref "R22") (pin "1") (pinfunction "1_1") (pintype "passive"))
      (node (ref "U2") (pin "6") (pinfunction "VOUT_6") (pintype "output"))
    )
    (net (code "74") (name "Net-(U3-REF)") (class "Default")
      (node (ref "R30") (pin "2") (pinfunction "2_2") (pintype "passive"))
      (node (ref "R31") (pin "1") (pinfunction "1_1") (pintype "passive"))
      (node (ref "U3") (pin "5") (pinfunction "REF_5") (pintype "passive"))
    )
    (net (code "75") (name "Net-(U3-VIN+)") (class "Default")
      (node (ref "C16") (pin "2") (pinfunction "2_2") (pintype "passive"))
      (node (ref "R25") (pin "1") (pinfunction "1_1") (pintype "passive"))
      (node (ref "U3") (pin "3") (pinfunction "VIN+_3") (pintype "input"))
    )
    (net (code "76") (name "Net-(U3-VIN-)") (class "Default")
      (node (ref "C16") (pin "1") (pinfunction "1_1") (pintype "passive"))
      (node (ref "R26") (pin "1") (pinfunction "1_1") (pintype "passive"))
      (node (ref "U3") (pin "2") (pinfunction "VIN-_2") (pintype "input"))
    )
    (net (code "77") (name "Net-(U3-VOUT)") (class "Default")
      (node (ref "R32") (pin "1") (pinfunction "1_1") (pintype "passive"))
      (node (ref "U3") (pin "6") (pinfunction "VOUT_6") (pintype "output"))
    )
    (net (code "78") (name "Net-(U4-REF)") (class "Default")
      (node (ref "R40") (pin "2") (pinfunction "2_2") (pintype "passive"))
      (node (ref "R41") (pin "1") (pinfunction "1_1") (pintype "passive"))
      (node (ref "U4") (pin "5") (pinfunction "REF_5") (pintype "passive"))
    )
    (net (code "79") (name "Net-(U4-VIN+)") (class "Default")
      (node (ref "C21") (pin "2") (pinfunction "2_2") (pintype "passive"))
      (node (ref "R35") (pin "1") (pinfunction "1_1") (pintype "passive"))
      (node (ref "U4") (pin "3") (pinfunction "VIN+_3") (pintype "input"))
    )
    (net (code "80") (name "Net-(U4-VIN-)") (class "Default")
      (node (ref "C21") (pin "1") (pinfunction "1_1") (pintype "passive"))
      (node (ref "R36") (pin "1") (pinfunction "1_1") (pintype "passive"))
      (node (ref "U4") (pin "2") (pinfunction "VIN-_2") (pintype "input"))
    )
    (net (code "81") (name "Net-(U4-VOUT)") (class "Default")
      (node (ref "R42") (pin "1") (pinfunction "1_1") (pintype "passive"))
      (node (ref "U4") (pin "6") (pinfunction "VOUT_6") (pintype "output"))
    )
    (net (code "82") (name "VDD3V3") (class "Default")
      (node (ref "C12") (pin "1") (pinfunction "1_1") (pintype "passive"))
      (node (ref "C17") (pin "1") (pinfunction "1_1") (pintype "passive"))
      (node (ref "C22") (pin "1") (pinfunction "1_1") (pintype "passive"))
      (node (ref "C7") (pin "1") (pinfunction "1_1") (pintype "passive"))
      (node (ref "JP1") (pin "6") (pinfunction "6_6") (pintype "passive"))
      (node (ref "JP2") (pin "4") (pinfunction "4_4") (pintype "passive"))
      (node (ref "R1") (pin "2") (pinfunction "2_2") (pintype "passive"))
      (node (ref "R10") (pin "1") (pinfunction "1_1") (pintype "passive"))
      (node (ref "R13") (pin "1") (pinfunction "1_1") (pintype "passive"))
      (node (ref "R20") (pin "1") (pinfunction "1_1") (pintype "passive"))
      (node (ref "R23") (pin "1") (pinfunction "1_1") (pintype "passive"))
      (node (ref "R3") (pin "1") (pinfunction "1_1") (pintype "passive"))
      (node (ref "R30") (pin "1") (pinfunction "1_1") (pintype "passive"))
      (node (ref "R33") (pin "1") (pinfunction "1_1") (pintype "passive"))
      (node (ref "R40") (pin "1") (pinfunction "1_1") (pintype "passive"))
      (node (ref "R43") (pin "1") (pinfunction "1_1") (pintype "passive"))
      (node (ref "U1") (pin "7") (pinfunction "V+_7") (pintype "power_in"))
      (node (ref "U2") (pin "7") (pinfunction "V+_7") (pintype "power_in"))
      (node (ref "U3") (pin "7") (pinfunction "V+_7") (pintype "power_in"))
      (node (ref "U4") (pin "7") (pinfunction "V+_7") (pintype "power_in"))
    )
    (net (code "83") (name "VDD33") (class "Default")
      (node (ref "C1") (pin "2") (pinfunction "2_2") (pintype "passive"))
      (node (ref "C2") (pin "2") (pinfunction "2_2") (pintype "passive"))
      (node (ref "R1") (pin "1") (pinfunction "1_1") (pintype "passive"))
      (node (ref "R2") (pin "2") (pinfunction "2_2") (pintype "passive"))
      (node (ref "U5") (pin "1") (pinfunction "VDDA_1") (pintype "passive"))
      (node (ref "U5") (pin "19") (pinfunction "VDD3P3_RTC_19") (pintype "passive"))
      (node (ref "U5") (pin "3") (pinfunction "VDDA3P3_3") (pintype "passive"))
      (node (ref "U5") (pin "37") (pinfunction "VDD3P3_CPU_37") (pintype "passive"))
      (node (ref "U5") (pin "4") (pinfunction "VDDA3P3_4") (pintype "passive"))
      (node (ref "U5") (pin "43") (pinfunction "VDDA_43") (pintype "passive"))
      (node (ref "U5") (pin "46") (pinfunction "VDDA_46") (pintype "passive"))
    )
    (net (code "84") (name "unconnected-(P1-Pad5)") (class "Default")
      (node (ref "P1") (pin "5") (pinfunction "5_5") (pintype "passive+no_connect"))
    )
    (net (code "85") (name "unconnected-(P2-Pad5)") (class "Default")
      (node (ref "P2") (pin "5") (pinfunction "5_5") (pintype "passive+no_connect"))
    )
    (net (code "86") (name "unconnected-(P3-Pad5)") (class "Default")
      (node (ref "P3") (pin "5") (pinfunction "5_5") (pintype "passive+no_connect"))
    )
    (net (code "87") (name "unconnected-(P4-Pad5)") (class "Default")
      (node (ref "P4") (pin "5") (pinfunction "5_5") (pintype "passive+no_connect"))
    )
    (net (code "88") (name "unconnected-(U5-CAP1_NC-Pad48)") (class "Default")
      (node (ref "U5") (pin "48") (pinfunction "CAP1_NC_48") (pintype "passive+no_connect"))
    )
    (net (code "89") (name "unconnected-(U5-CAP2_NC-Pad47)") (class "Default")
      (node (ref "U5") (pin "47") (pinfunction "CAP2_NC_47") (pintype "passive+no_connect"))
    )
    (net (code "90") (name "unconnected-(U5-LNA_IN-Pad2)") (class "Default")
      (node (ref "U5") (pin "2") (pinfunction "LNA_IN_2") (pintype "passive+no_connect"))
    )
    (net (code "91") (name "unconnected-(U5-VDD_SDIO-Pad26)") (class "Default")
      (node (ref "U5") (pin "26") (pinfunction "VDD_SDIO_26") (pintype "passive+no_connect"))
    )
    (net (code "92") (name "unconnected-(U5-XTAL_N_NC-Pad44)") (class "Default")
      (node (ref "U5") (pin "44") (pinfunction "XTAL_N_NC_44") (pintype "passive+no_connect"))
    )
    (net (code "93") (name "unconnected-(U5-XTAL_P_NC-Pad45)") (class "Default")
      (node (ref "U5") (pin "45") (pinfunction "XTAL_P_NC_45") (pintype "passive+no_connect"))
    )
  )
)
